# LIM_LEDS_POWER.net
KiCad netlist of a schematic drawn in Altium Designer
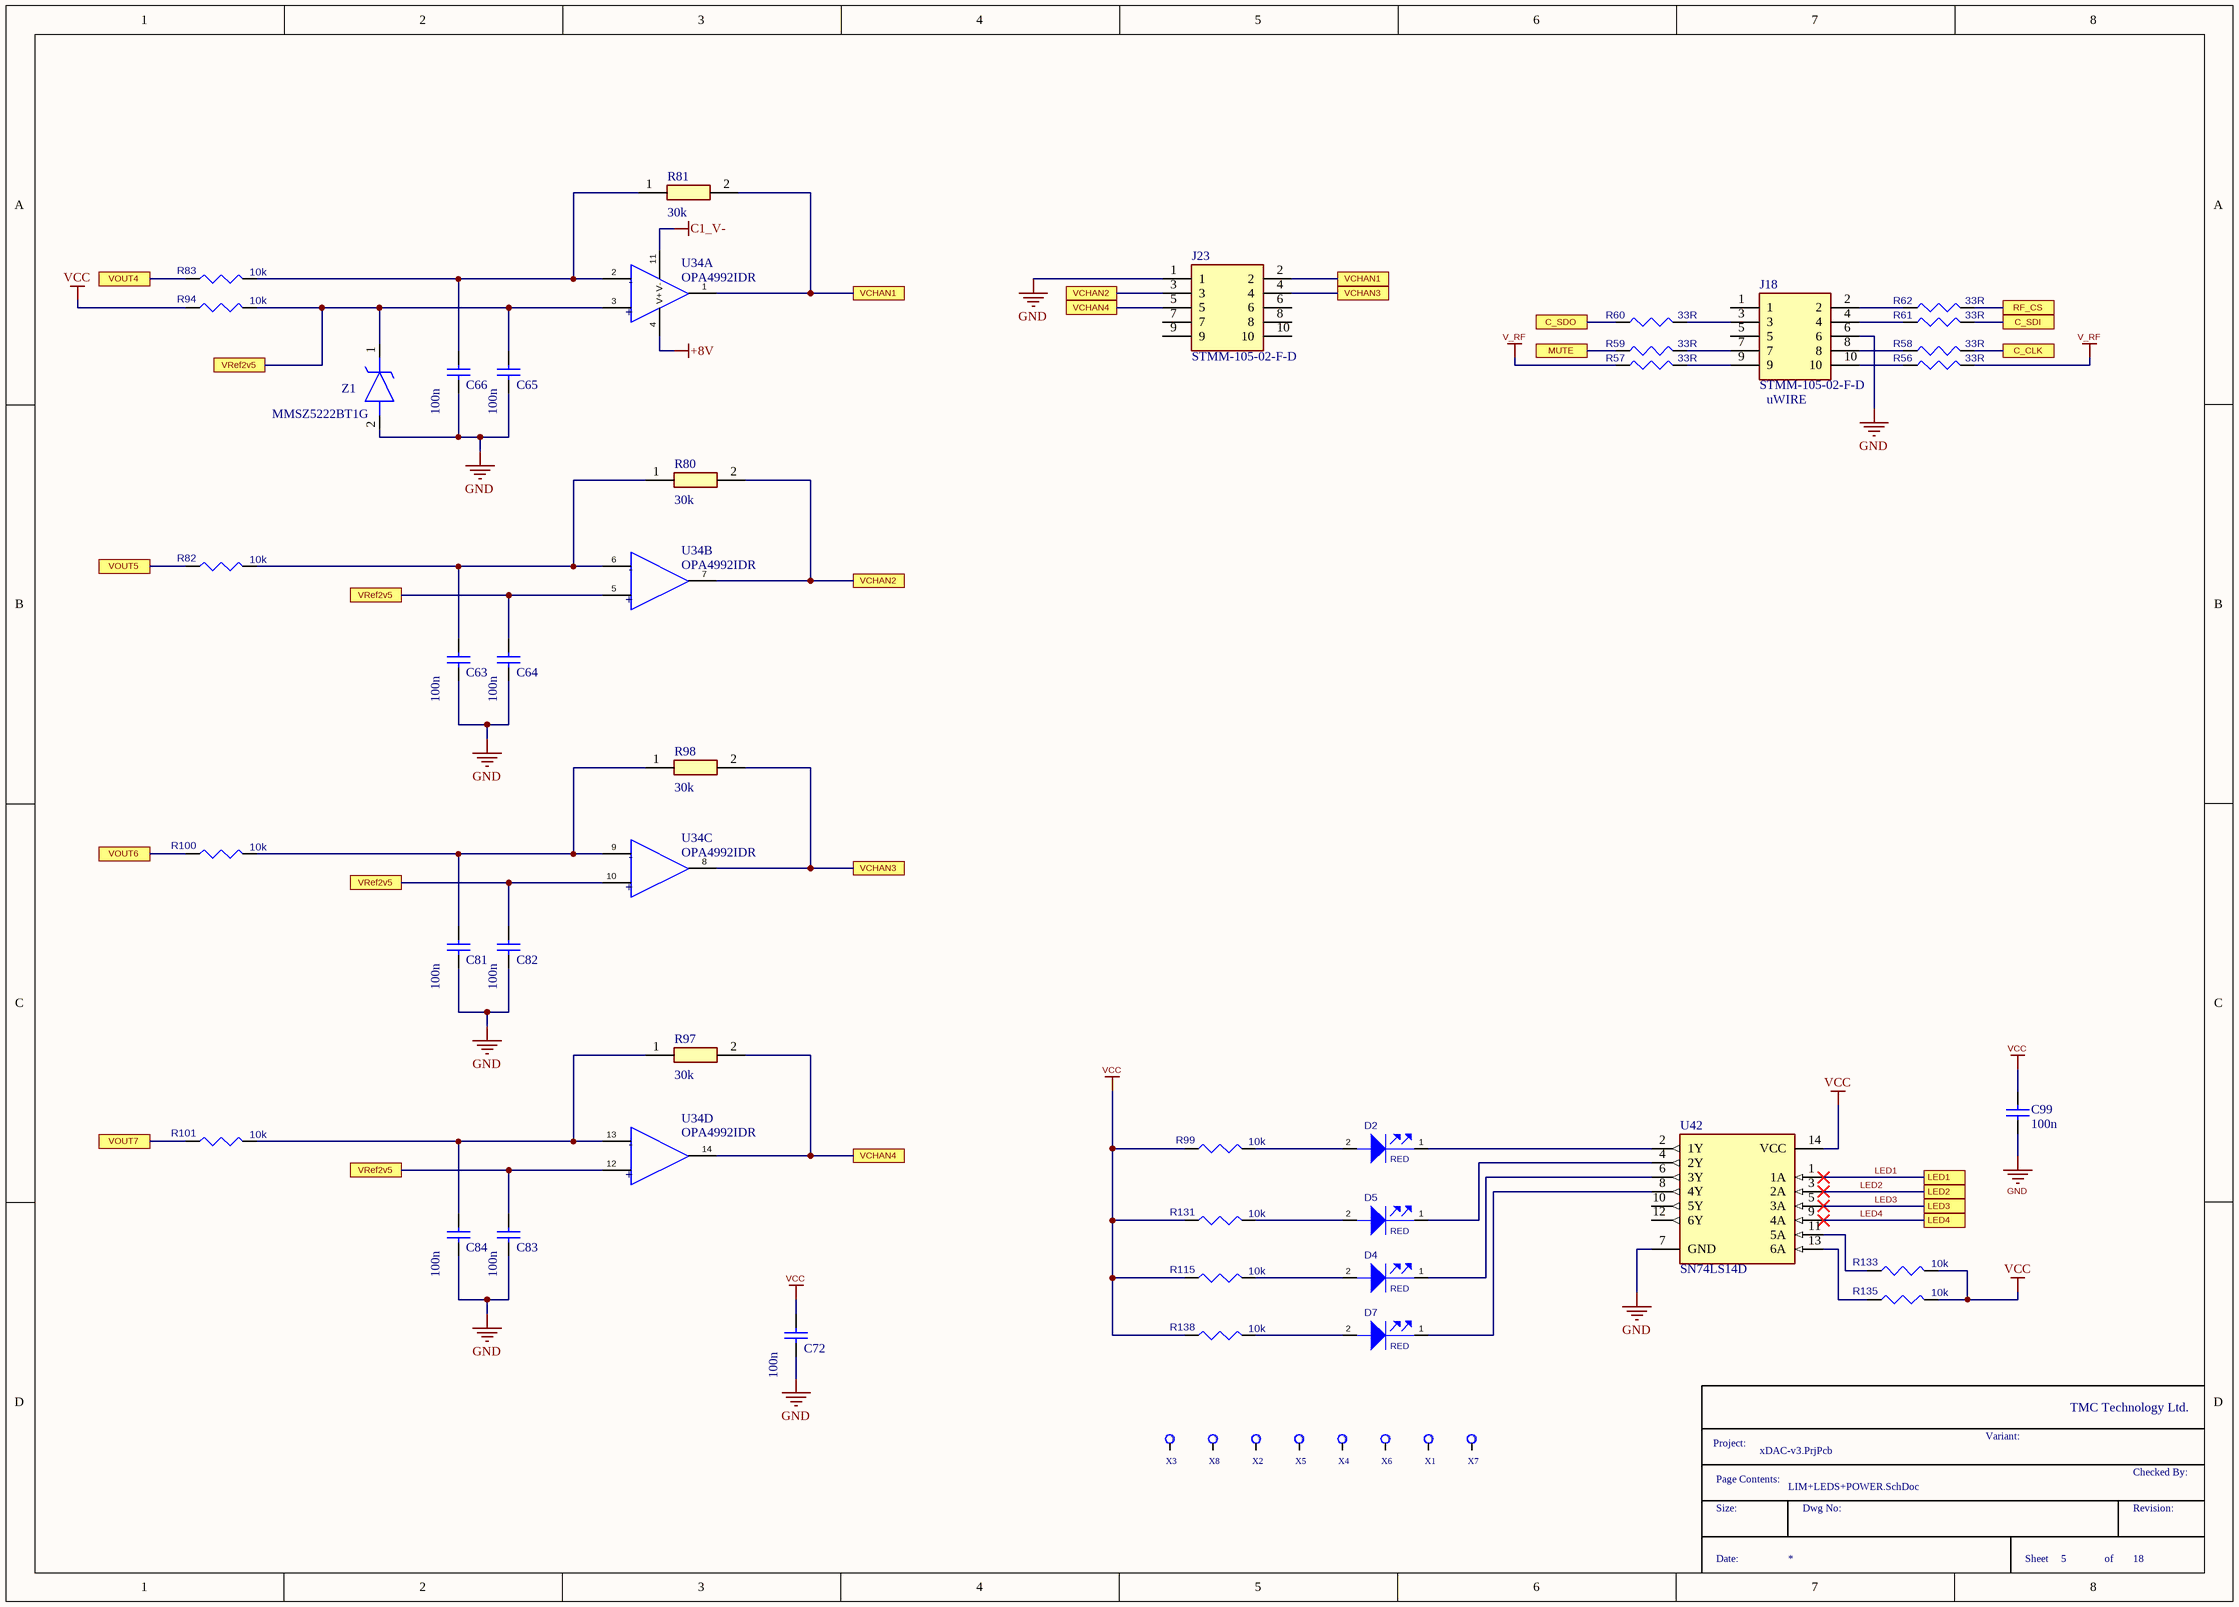
[diagram p0: LIM+LEDS+POWER.SchDoc]

(export (version "E")
  (design (tool "Eeschema 10.0.6"))
  (components
    (comp (ref "C63")
      (value "100n")
      (footprint "CAPC1608X90X35LL15T15")
      (description "Chip Capacitor, 100 nF, +/- 10%, 50 V, -55 to 125 degC, 0603 (1608 Metric), RoHS, Tape and Reel")
      (fields (field (name "TOLERANCE") "10%") (field (name "MANUFACTURER") "KEMET"))
      (libsource (lib "xDAC_Carrier") (part "CMP-1035-02592-3"))
    )
    (comp (ref "C64")
      (value "100n")
      (footprint "CAPC1608X90X35LL15T15")
      (description "Chip Capacitor, 100 nF, +/- 10%, 50 V, -55 to 125 degC, 0603 (1608 Metric), RoHS, Tape and Reel")
      (fields (field (name "TOLERANCE") "10%") (field (name "MANUFACTURER") "KEMET"))
      (libsource (lib "xDAC_Carrier") (part "CMP-1035-02592-3"))
    )
    (comp (ref "C65")
      (value "100n")
      (footprint "CAPC1608X90X35LL15T15")
      (description "Chip Capacitor, 100 nF, +/- 10%, 50 V, -55 to 125 degC, 0603 (1608 Metric), RoHS, Tape and Reel")
      (fields (field (name "TOLERANCE") "10%") (field (name "MANUFACTURER") "KEMET"))
      (libsource (lib "xDAC_Carrier") (part "CMP-1035-02592-3"))
    )
    (comp (ref "C66")
      (value "100n")
      (footprint "CAPC1608X90X35LL15T15")
      (description "Chip Capacitor, 100 nF, +/- 10%, 50 V, -55 to 125 degC, 0603 (1608 Metric), RoHS, Tape and Reel")
      (fields (field (name "TOLERANCE") "10%") (field (name "MANUFACTURER") "KEMET"))
      (libsource (lib "xDAC_Carrier") (part "CMP-1035-02592-3"))
    )
    (comp (ref "C72")
      (value "100n")
      (footprint "CAPC1608X90X35LL15T15")
      (description "Chip Capacitor, 100 nF, +/- 10%, 50 V, -55 to 125 degC, 0603 (1608 Metric), RoHS, Tape and Reel")
      (fields (field (name "TOLERANCE") "10%") (field (name "MANUFACTURER") "KEMET"))
      (libsource (lib "xDAC_Carrier") (part "CMP-1035-02592-3"))
    )
    (comp (ref "C81")
      (value "100n")
      (footprint "CAPC1608X90X35LL15T15")
      (description "Chip Capacitor, 100 nF, +/- 10%, 50 V, -55 to 125 degC, 0603 (1608 Metric), RoHS, Tape and Reel")
      (fields (field (name "TOLERANCE") "10%") (field (name "MANUFACTURER") "KEMET"))
      (libsource (lib "xDAC_Carrier") (part "CMP-1035-02592-3"))
    )
    (comp (ref "C82")
      (value "100n")
      (footprint "CAPC1608X90X35LL15T15")
      (description "Chip Capacitor, 100 nF, +/- 10%, 50 V, -55 to 125 degC, 0603 (1608 Metric), RoHS, Tape and Reel")
      (fields (field (name "TOLERANCE") "10%") (field (name "MANUFACTURER") "KEMET"))
      (libsource (lib "xDAC_Carrier") (part "CMP-1035-02592-3"))
    )
    (comp (ref "C83")
      (value "100n")
      (footprint "CAPC1608X90X35LL15T15")
      (description "Chip Capacitor, 100 nF, +/- 10%, 50 V, -55 to 125 degC, 0603 (1608 Metric), RoHS, Tape and Reel")
      (fields (field (name "TOLERANCE") "10%") (field (name "MANUFACTURER") "KEMET"))
      (libsource (lib "xDAC_Carrier") (part "CMP-1035-02592-3"))
    )
    (comp (ref "C84")
      (value "100n")
      (footprint "CAPC1608X90X35LL15T15")
      (description "Chip Capacitor, 100 nF, +/- 10%, 50 V, -55 to 125 degC, 0603 (1608 Metric), RoHS, Tape and Reel")
      (fields (field (name "TOLERANCE") "10%") (field (name "MANUFACTURER") "KEMET"))
      (libsource (lib "xDAC_Carrier") (part "CMP-1035-02592-3"))
    )
    (comp (ref "C99")
      (value "100n")
      (footprint "CAPC1608X90X35LL15T15")
      (description "Chip Capacitor, 100 nF, +/- 10%, 50 V, -55 to 125 degC, 0603 (1608 Metric), RoHS, Tape and Reel")
      (fields (field (name "TOLERANCE") "10%") (field (name "MANUFACTURER") "KEMET"))
      (libsource (lib "xDAC_Carrier") (part "CMP-1035-02592-3"))
    )
    (comp (ref "D2")
      (value "RED")
      (footprint "LED$2F$RA")
      (description "LED,RED,WATERCLEAR,TH RA")
      (fields (field (name "MANUFACTURER") "BROADCOM") (field (name "PART NO") "HLMP-3301-F00B2"))
      (libsource (lib "xDAC_Carrier") (part "LED"))
    )
    (comp (ref "D4")
      (value "RED")
      (footprint "LED$2F$RA")
      (description "LED,RED,WATERCLEAR,TH RA")
      (fields (field (name "MANUFACTURER") "BROADCOM") (field (name "PART NO") "HLMP-3301-F00B2"))
      (libsource (lib "xDAC_Carrier") (part "LED"))
    )
    (comp (ref "D5")
      (value "RED")
      (footprint "LED$2F$RA")
      (description "LED,RED,WATERCLEAR,TH RA")
      (fields (field (name "MANUFACTURER") "BROADCOM") (field (name "PART NO") "HLMP-3301-F00B2"))
      (libsource (lib "xDAC_Carrier") (part "LED"))
    )
    (comp (ref "D7")
      (value "RED")
      (footprint "LED$2F$RA")
      (description "LED,RED,WATERCLEAR,TH RA")
      (fields (field (name "MANUFACTURER") "BROADCOM") (field (name "PART NO") "HLMP-3301-F00B2"))
      (libsource (lib "xDAC_Carrier") (part "LED"))
    )
    (comp (ref "J18")
      (value "STMM-105-02-F-D")
      (footprint "STMM-105-XX-YY-D")
      (description "Connector")
      (fields (field (name "MOUSER PART NUMBER") "200-STMM10502FD") (field (name "ALTIUM_VALUE") "uWIRE"))
      (libsource (lib "xDAC_Carrier") (part "STMM-105-02-F-D"))
    )
    (comp (ref "J23")
      (value "STMM-105-02-F-D")
      (footprint "STMM-105-XX-YY-D")
      (description "Connector")
      (fields (field (name "MOUSER PART NUMBER") "200-STMM10502FD"))
      (libsource (lib "xDAC_Carrier") (part "STMM-105-02-F-D"))
    )
    (comp (ref "R56")
      (value "33R")
      (footprint "CR0603N")
      (description "RES.,10k OHMS,1%,1/10W,0603")
      (fields (field (name "MANUFACTURER") "PANASONIC") (field (name "TOLERANCE") "1%"))
      (libsource (lib "xDAC_Carrier") (part "RES"))
    )
    (comp (ref "R57")
      (value "33R")
      (footprint "CR0603N")
      (description "RES.,10k OHMS,1%,1/10W,0603")
      (fields (field (name "MANUFACTURER") "PANASONIC") (field (name "TOLERANCE") "1%"))
      (libsource (lib "xDAC_Carrier") (part "RES"))
    )
    (comp (ref "R58")
      (value "33R")
      (footprint "CR0603N")
      (description "RES.,10k OHMS,1%,1/10W,0603")
      (fields (field (name "MANUFACTURER") "PANASONIC") (field (name "TOLERANCE") "1%"))
      (libsource (lib "xDAC_Carrier") (part "RES"))
    )
    (comp (ref "R59")
      (value "33R")
      (footprint "CR0603N")
      (description "RES.,10k OHMS,1%,1/10W,0603")
      (fields (field (name "MANUFACTURER") "PANASONIC") (field (name "TOLERANCE") "1%"))
      (libsource (lib "xDAC_Carrier") (part "RES"))
    )
    (comp (ref "R60")
      (value "33R")
      (footprint "CR0603N")
      (description "RES.,10k OHMS,1%,1/10W,0603")
      (fields (field (name "MANUFACTURER") "PANASONIC") (field (name "TOLERANCE") "1%"))
      (libsource (lib "xDAC_Carrier") (part "RES"))
    )
    (comp (ref "R61")
      (value "33R")
      (footprint "CR0603N")
      (description "RES.,10k OHMS,1%,1/10W,0603")
      (fields (field (name "MANUFACTURER") "PANASONIC") (field (name "TOLERANCE") "1%"))
      (libsource (lib "xDAC_Carrier") (part "RES"))
    )
    (comp (ref "R62")
      (value "33R")
      (footprint "CR0603N")
      (description "RES.,10k OHMS,1%,1/10W,0603")
      (fields (field (name "MANUFACTURER") "PANASONIC") (field (name "TOLERANCE") "1%"))
      (libsource (lib "xDAC_Carrier") (part "RES"))
    )
    (comp (ref "R80")
      (value "30k")
      (footprint "ERJS03J155V")
      (description "Resistor")
      (fields (field (name "MANUFACTURER_PART_NUMBER") "ERJ-U03F3002V"))
      (libsource (lib "Pilot") (part "ERJ-U03F3002V"))
    )
    (comp (ref "R81")
      (value "30k")
      (footprint "ERJS03J155V")
      (description "Resistor")
      (fields (field (name "MANUFACTURER_PART_NUMBER") "ERJ-U03F3002V"))
      (libsource (lib "Pilot") (part "ERJ-U03F3002V"))
    )
    (comp (ref "R82")
      (value "10k")
      (footprint "CR0603N")
      (description "RES.,10k OHMS,1%,1/10W,0603")
      (fields (field (name "MANUFACTURER") "PANASONIC") (field (name "TOLERANCE") "1%"))
      (libsource (lib "xDAC_Carrier") (part "RES"))
    )
    (comp (ref "R83")
      (value "10k")
      (footprint "CR0603N")
      (description "RES.,10k OHMS,1%,1/10W,0603")
      (fields (field (name "MANUFACTURER") "PANASONIC") (field (name "TOLERANCE") "1%"))
      (libsource (lib "xDAC_Carrier") (part "RES"))
    )
    (comp (ref "R94")
      (value "10k")
      (footprint "CR0603N")
      (description "RES.,10k OHMS,1%,1/10W,0603")
      (fields (field (name "MANUFACTURER") "PANASONIC") (field (name "TOLERANCE") "1%"))
      (libsource (lib "xDAC_Carrier") (part "RES"))
    )
    (comp (ref "R97")
      (value "30k")
      (footprint "ERJS03J155V")
      (description "Resistor")
      (fields (field (name "MANUFACTURER_PART_NUMBER") "ERJ-U03F3002V"))
      (libsource (lib "Pilot") (part "ERJ-U03F3002V"))
    )
    (comp (ref "R98")
      (value "30k")
      (footprint "ERJS03J155V")
      (description "Resistor")
      (fields (field (name "MANUFACTURER_PART_NUMBER") "ERJ-U03F3002V"))
      (libsource (lib "Pilot") (part "ERJ-U03F3002V"))
    )
    (comp (ref "R99")
      (value "10k")
      (footprint "CR0603N")
      (description "RES.,10k OHMS,1%,1/10W,0603")
      (fields (field (name "MANUFACTURER") "PANASONIC") (field (name "TOLERANCE") "1%"))
      (libsource (lib "xDAC_Carrier") (part "RES"))
    )
    (comp (ref "R100")
      (value "10k")
      (footprint "CR0603N")
      (description "RES.,10k OHMS,1%,1/10W,0603")
      (fields (field (name "MANUFACTURER") "PANASONIC") (field (name "TOLERANCE") "1%"))
      (libsource (lib "xDAC_Carrier") (part "RES"))
    )
    (comp (ref "R101")
      (value "10k")
      (footprint "CR0603N")
      (description "RES.,10k OHMS,1%,1/10W,0603")
      (fields (field (name "MANUFACTURER") "PANASONIC") (field (name "TOLERANCE") "1%"))
      (libsource (lib "xDAC_Carrier") (part "RES"))
    )
    (comp (ref "R115")
      (value "10k")
      (footprint "CR0603N")
      (description "RES.,10k OHMS,1%,1/10W,0603")
      (fields (field (name "MANUFACTURER") "PANASONIC") (field (name "TOLERANCE") "1%"))
      (libsource (lib "xDAC_Carrier") (part "RES"))
    )
    (comp (ref "R131")
      (value "10k")
      (footprint "CR0603N")
      (description "RES.,10k OHMS,1%,1/10W,0603")
      (fields (field (name "MANUFACTURER") "PANASONIC") (field (name "TOLERANCE") "1%"))
      (libsource (lib "xDAC_Carrier") (part "RES"))
    )
    (comp (ref "R133")
      (value "10k")
      (footprint "CR0603N")
      (description "RES.,10k OHMS,1%,1/10W,0603")
      (fields (field (name "MANUFACTURER") "PANASONIC") (field (name "TOLERANCE") "1%"))
      (libsource (lib "xDAC_Carrier") (part "RES"))
    )
    (comp (ref "R135")
      (value "10k")
      (footprint "CR0603N")
      (description "RES.,10k OHMS,1%,1/10W,0603")
      (fields (field (name "MANUFACTURER") "PANASONIC") (field (name "TOLERANCE") "1%"))
      (libsource (lib "xDAC_Carrier") (part "RES"))
    )
    (comp (ref "R138")
      (value "10k")
      (footprint "CR0603N")
      (description "RES.,10k OHMS,1%,1/10W,0603")
      (fields (field (name "MANUFACTURER") "PANASONIC") (field (name "TOLERANCE") "1%"))
      (libsource (lib "xDAC_Carrier") (part "RES"))
    )
    (comp (ref "U34")
      (value "OPA4992IDR")
      (footprint "SOIC127P600X175-14N")
      (description "Integrated Circuit")
      (fields (field (name "MOUSER PART NUMBER") "595-OPA4992IDR"))
      (libsource (lib "xDAC_Carrier") (part "OPA4992IDR"))
    )
    (comp (ref "U42")
      (value "SN74LS14D")
      (footprint "FP-D0014A-MFG")
      (description "IC INVERTER SCHMITT 6CH 14SOIC")
      (fields
        (field (name "OCTOPART") "https://octopart.com/sn74ls14d-texas+instruments-464458")
        (field (name "MANUFACTURER") "Texas Instruments")
      )
      (libsource (lib "Altium Content Vault") (part "988d500a1b54a36af656cee24e4e601"))
    )
    (comp (ref "X1")
      (value "MTG3MM")
      (footprint "MTG3MM")
      (description ".128 MOUNTING HOLE / .250 PAD")
      (fields
        (field (name "PART NUMBER") "MTHOLE1")
        (field (name "CREATED BY") "CADPRO, SAN DIEGO, CA  (619) 552-1475")
      )
      (libsource (lib "xDAC_Carrier") (part "MTG3MM"))
    )
    (comp (ref "X2")
      (value "MTG3MM")
      (footprint "MTG3MM")
      (description ".128 MOUNTING HOLE / .250 PAD")
      (fields
        (field (name "PART NUMBER") "MTHOLE1")
        (field (name "CREATED BY") "CADPRO, SAN DIEGO, CA  (619) 552-1475")
      )
      (libsource (lib "xDAC_Carrier") (part "MTG3MM"))
    )
    (comp (ref "X3")
      (value "MTG3MM")
      (footprint "MTG3MM")
      (description ".128 MOUNTING HOLE / .250 PAD")
      (fields
        (field (name "PART NUMBER") "MTHOLE1")
        (field (name "CREATED BY") "CADPRO, SAN DIEGO, CA  (619) 552-1475")
      )
      (libsource (lib "xDAC_Carrier") (part "MTG3MM"))
    )
    (comp (ref "X4")
      (value "MTG3MM")
      (footprint "MTG3MM")
      (description ".128 MOUNTING HOLE / .250 PAD")
      (fields
        (field (name "PART NUMBER") "MTHOLE1")
        (field (name "CREATED BY") "CADPRO, SAN DIEGO, CA  (619) 552-1475")
      )
      (libsource (lib "xDAC_Carrier") (part "MTG3MM"))
    )
    (comp (ref "X5")
      (value "MTG3MM")
      (footprint "MTG3MM")
      (description ".128 MOUNTING HOLE / .250 PAD")
      (fields
        (field (name "PART NUMBER") "MTHOLE1")
        (field (name "CREATED BY") "CADPRO, SAN DIEGO, CA  (619) 552-1475")
      )
      (libsource (lib "xDAC_Carrier") (part "MTG3MM"))
    )
    (comp (ref "X6")
      (value "MTG3MM")
      (footprint "MTG3MM")
      (description ".128 MOUNTING HOLE / .250 PAD")
      (fields
        (field (name "PART NUMBER") "MTHOLE1")
        (field (name "CREATED BY") "CADPRO, SAN DIEGO, CA  (619) 552-1475")
      )
      (libsource (lib "xDAC_Carrier") (part "MTG3MM"))
    )
    (comp (ref "X7")
      (value "MTG3MM")
      (footprint "MTG3MM")
      (description ".128 MOUNTING HOLE / .250 PAD")
      (fields
        (field (name "PART NUMBER") "MTHOLE1")
        (field (name "CREATED BY") "CADPRO, SAN DIEGO, CA  (619) 552-1475")
      )
      (libsource (lib "xDAC_Carrier") (part "MTG3MM"))
    )
    (comp (ref "X8")
      (value "MTG3MM")
      (footprint "MTG3MM")
      (description ".128 MOUNTING HOLE / .250 PAD")
      (fields
        (field (name "PART NUMBER") "MTHOLE1")
        (field (name "CREATED BY") "CADPRO, SAN DIEGO, CA  (619) 552-1475")
      )
      (libsource (lib "xDAC_Carrier") (part "MTG3MM"))
    )
    (comp (ref "Z1")
      (value "MMSZ5222BT1G")
      (footprint "SOD3716X135N")
      (description "Zener Diode")
      (fields (field (name "MOUSER PART NUMBER") "863-MMSZ5222BT1G"))
      (libsource (lib "xDAC_Carrier") (part "MMSZ5222BT1G"))
    )
  )
  (nets
    (net (code "1") (name "+8V") (class "Default")
      (node (ref "U34") (pin "4") (pinfunction "V+_4") (pintype "passive"))
    )
    (net (code "2") (name "/C_CLK") (class "Default")
      (node (ref "R58") (pin "2") (pinfunction "2_2") (pintype "passive"))
    )
    (net (code "3") (name "/C_SDI") (class "Default")
      (node (ref "R61") (pin "2") (pinfunction "2_2") (pintype "passive"))
    )
    (net (code "4") (name "/C_SDO") (class "Default")
      (node (ref "R60") (pin "1") (pinfunction "1_1") (pintype "passive"))
    )
    (net (code "5") (name "/LED1") (class "Default")
      (node (ref "U42") (pin "1") (pinfunction "1A_1") (pintype "input+no_connect"))
    )
    (net (code "6") (name "/LED2") (class "Default")
      (node (ref "U42") (pin "3") (pinfunction "2A_3") (pintype "input+no_connect"))
    )
    (net (code "7") (name "/LED3") (class "Default")
      (node (ref "U42") (pin "5") (pinfunction "3A_5") (pintype "input+no_connect"))
    )
    (net (code "8") (name "/LED4") (class "Default")
      (node (ref "U42") (pin "9") (pinfunction "4A_9") (pintype "input+no_connect"))
    )
    (net (code "9") (name "/MUTE") (class "Default")
      (node (ref "R59") (pin "1") (pinfunction "1_1") (pintype "passive"))
    )
    (net (code "10") (name "/RF_CS") (class "Default")
      (node (ref "R62") (pin "2") (pinfunction "2_2") (pintype "passive"))
    )
    (net (code "11") (name "/VCHAN1") (class "Default")
      (node (ref "J23") (pin "2") (pinfunction "2_2") (pintype "passive"))
      (node (ref "R81") (pin "2") (pinfunction "2_2") (pintype "passive"))
      (node (ref "U34") (pin "1") (pinfunction "1_1") (pintype "passive"))
    )
    (net (code "12") (name "/VCHAN2") (class "Default")
      (node (ref "J23") (pin "3") (pinfunction "3_3") (pintype "passive"))
      (node (ref "R80") (pin "2") (pinfunction "2_2") (pintype "passive"))
      (node (ref "U34") (pin "7") (pinfunction "7_7") (pintype "passive"))
    )
    (net (code "13") (name "/VCHAN3") (class "Default")
      (node (ref "J23") (pin "4") (pinfunction "4_4") (pintype "passive"))
      (node (ref "R98") (pin "2") (pinfunction "2_2") (pintype "passive"))
      (node (ref "U34") (pin "8") (pinfunction "8_8") (pintype "passive"))
    )
    (net (code "14") (name "/VCHAN4") (class "Default")
      (node (ref "J23") (pin "5") (pinfunction "5_5") (pintype "passive"))
      (node (ref "R97") (pin "2") (pinfunction "2_2") (pintype "passive"))
      (node (ref "U34") (pin "14") (pinfunction "14_14") (pintype "passive"))
    )
    (net (code "15") (name "/VOUT4") (class "Default")
      (node (ref "R83") (pin "1") (pinfunction "1_1") (pintype "passive"))
    )
    (net (code "16") (name "/VOUT5") (class "Default")
      (node (ref "R82") (pin "1") (pinfunction "1_1") (pintype "passive"))
    )
    (net (code "17") (name "/VOUT6") (class "Default")
      (node (ref "R100") (pin "1") (pinfunction "1_1") (pintype "passive"))
    )
    (net (code "18") (name "/VOUT7") (class "Default")
      (node (ref "R101") (pin "1") (pinfunction "1_1") (pintype "passive"))
    )
    (net (code "19") (name "/VRef2v5") (class "Default")
      (node (ref "C64") (pin "1") (pinfunction "1_1") (pintype "passive"))
      (node (ref "C65") (pin "1") (pinfunction "1_1") (pintype "passive"))
      (node (ref "C82") (pin "1") (pinfunction "1_1") (pintype "passive"))
      (node (ref "C83") (pin "1") (pinfunction "1_1") (pintype "passive"))
      (node (ref "R94") (pin "2") (pinfunction "2_2") (pintype "passive"))
      (node (ref "U34") (pin "10") (pinfunction "10_10") (pintype "passive"))
      (node (ref "U34") (pin "12") (pinfunction "12_12") (pintype "passive"))
      (node (ref "U34") (pin "3") (pinfunction "3_3") (pintype "passive"))
      (node (ref "U34") (pin "5") (pinfunction "5_5") (pintype "passive"))
      (node (ref "Z1") (pin "1") (pinfunction "K_1") (pintype "passive"))
    )
    (net (code "20") (name "C1_V-") (class "Default")
      (node (ref "U34") (pin "11") (pinfunction "V-_11") (pintype "passive"))
    )
    (net (code "21") (name "GND") (class "Default")
      (node (ref "C63") (pin "2") (pinfunction "2_2") (pintype "passive"))
      (node (ref "C64") (pin "2") (pinfunction "2_2") (pintype "passive"))
      (node (ref "C65") (pin "2") (pinfunction "2_2") (pintype "passive"))
      (node (ref "C66") (pin "2") (pinfunction "2_2") (pintype "passive"))
      (node (ref "C72") (pin "2") (pinfunction "2_2") (pintype "passive"))
      (node (ref "C81") (pin "2") (pinfunction "2_2") (pintype "passive"))
      (node (ref "C82") (pin "2") (pinfunction "2_2") (pintype "passive"))
      (node (ref "C83") (pin "2") (pinfunction "2_2") (pintype "passive"))
      (node (ref "C84") (pin "2") (pinfunction "2_2") (pintype "passive"))
      (node (ref "C99") (pin "2") (pinfunction "2_2") (pintype "passive"))
      (node (ref "J18") (pin "6") (pinfunction "6_6") (pintype "passive"))
      (node (ref "J23") (pin "1") (pinfunction "1_1") (pintype "passive"))
      (node (ref "U42") (pin "7") (pinfunction "GND_7") (pintype "passive"))
      (node (ref "Z1") (pin "2") (pinfunction "A_2") (pintype "passive"))
    )
    (net (code "22") (name "Net-(C63-Pad1)") (class "Default")
      (node (ref "C63") (pin "1") (pinfunction "1_1") (pintype "passive"))
      (node (ref "R80") (pin "1") (pinfunction "1_1") (pintype "passive"))
      (node (ref "R82") (pin "2") (pinfunction "2_2") (pintype "passive"))
      (node (ref "U34") (pin "6") (pinfunction "6_6") (pintype "passive"))
    )
    (net (code "23") (name "Net-(C66-Pad1)") (class "Default")
      (node (ref "C66") (pin "1") (pinfunction "1_1") (pintype "passive"))
      (node (ref "R81") (pin "1") (pinfunction "1_1") (pintype "passive"))
      (node (ref "R83") (pin "2") (pinfunction "2_2") (pintype "passive"))
      (node (ref "U34") (pin "2") (pinfunction "2_2") (pintype "passive"))
    )
    (net (code "24") (name "Net-(C81-Pad1)") (class "Default")
      (node (ref "C81") (pin "1") (pinfunction "1_1") (pintype "passive"))
      (node (ref "R100") (pin "2") (pinfunction "2_2") (pintype "passive"))
      (node (ref "R98") (pin "1") (pinfunction "1_1") (pintype "passive"))
      (node (ref "U34") (pin "9") (pinfunction "9_9") (pintype "passive"))
    )
    (net (code "25") (name "Net-(C84-Pad1)") (class "Default")
      (node (ref "C84") (pin "1") (pinfunction "1_1") (pintype "passive"))
      (node (ref "R101") (pin "2") (pinfunction "2_2") (pintype "passive"))
      (node (ref "R97") (pin "1") (pinfunction "1_1") (pintype "passive"))
      (node (ref "U34") (pin "13") (pinfunction "13_13") (pintype "passive"))
    )
    (net (code "26") (name "Net-(D2-ANODE)") (class "Default")
      (node (ref "D2") (pin "2") (pinfunction "ANODE_2") (pintype "passive"))
      (node (ref "R99") (pin "2") (pinfunction "2_2") (pintype "passive"))
    )
    (net (code "27") (name "Net-(D2-CATHODE)") (class "Default")
      (node (ref "D2") (pin "1") (pinfunction "CATHODE_1") (pintype "passive"))
      (node (ref "U42") (pin "2") (pinfunction "1Y_2") (pintype "output"))
    )
    (net (code "28") (name "Net-(D4-ANODE)") (class "Default")
      (node (ref "D4") (pin "2") (pinfunction "ANODE_2") (pintype "passive"))
      (node (ref "R115") (pin "2") (pinfunction "2_2") (pintype "passive"))
    )
    (net (code "29") (name "Net-(D4-CATHODE)") (class "Default")
      (node (ref "D4") (pin "1") (pinfunction "CATHODE_1") (pintype "passive"))
      (node (ref "U42") (pin "6") (pinfunction "3Y_6") (pintype "output"))
    )
    (net (code "30") (name "Net-(D5-ANODE)") (class "Default")
      (node (ref "D5") (pin "2") (pinfunction "ANODE_2") (pintype "passive"))
      (node (ref "R131") (pin "2") (pinfunction "2_2") (pintype "passive"))
    )
    (net (code "31") (name "Net-(D5-CATHODE)") (class "Default")
      (node (ref "D5") (pin "1") (pinfunction "CATHODE_1") (pintype "passive"))
      (node (ref "U42") (pin "4") (pinfunction "2Y_4") (pintype "output"))
    )
    (net (code "32") (name "Net-(D7-ANODE)") (class "Default")
      (node (ref "D7") (pin "2") (pinfunction "ANODE_2") (pintype "passive"))
      (node (ref "R138") (pin "2") (pinfunction "2_2") (pintype "passive"))
    )
    (net (code "33") (name "Net-(D7-CATHODE)") (class "Default")
      (node (ref "D7") (pin "1") (pinfunction "CATHODE_1") (pintype "passive"))
      (node (ref "U42") (pin "8") (pinfunction "4Y_8") (pintype "output"))
    )
    (net (code "34") (name "Net-(J18-Pad2)") (class "Default")
      (node (ref "J18") (pin "2") (pinfunction "2_2") (pintype "passive"))
      (node (ref "R62") (pin "1") (pinfunction "1_1") (pintype "passive"))
    )
    (net (code "35") (name "Net-(J18-Pad3)") (class "Default")
      (node (ref "J18") (pin "3") (pinfunction "3_3") (pintype "passive"))
      (node (ref "R60") (pin "2") (pinfunction "2_2") (pintype "passive"))
    )
    (net (code "36") (name "Net-(J18-Pad4)") (class "Default")
      (node (ref "J18") (pin "4") (pinfunction "4_4") (pintype "passive"))
      (node (ref "R61") (pin "1") (pinfunction "1_1") (pintype "passive"))
    )
    (net (code "37") (name "Net-(J18-Pad7)") (class "Default")
      (node (ref "J18") (pin "7") (pinfunction "7_7") (pintype "passive"))
      (node (ref "R59") (pin "2") (pinfunction "2_2") (pintype "passive"))
    )
    (net (code "38") (name "Net-(J18-Pad8)") (class "Default")
      (node (ref "J18") (pin "8") (pinfunction "8_8") (pintype "passive"))
      (node (ref "R58") (pin "1") (pinfunction "1_1") (pintype "passive"))
    )
    (net (code "39") (name "Net-(J18-Pad9)") (class "Default")
      (node (ref "J18") (pin "9") (pinfunction "9_9") (pintype "passive"))
      (node (ref "R57") (pin "2") (pinfunction "2_2") (pintype "passive"))
    )
    (net (code "40") (name "Net-(J18-Pad10)") (class "Default")
      (node (ref "J18") (pin "10") (pinfunction "10_10") (pintype "passive"))
      (node (ref "R56") (pin "1") (pinfunction "1_1") (pintype "passive"))
    )
    (net (code "41") (name "Net-(U42-5A)") (class "Default")
      (node (ref "R133") (pin "1") (pinfunction "1_1") (pintype "passive"))
      (node (ref "U42") (pin "11") (pinfunction "5A_11") (pintype "input"))
    )
    (net (code "42") (name "Net-(U42-6A)") (class "Default")
      (node (ref "R135") (pin "1") (pinfunction "1_1") (pintype "passive"))
      (node (ref "U42") (pin "13") (pinfunction "6A_13") (pintype "input"))
    )
    (net (code "43") (name "VCC") (class "Default")
      (node (ref "C72") (pin "1") (pinfunction "1_1") (pintype "passive"))
      (node (ref "C99") (pin "1") (pinfunction "1_1") (pintype "passive"))
      (node (ref "R115") (pin "1") (pinfunction "1_1") (pintype "passive"))
      (node (ref "R131") (pin "1") (pinfunction "1_1") (pintype "passive"))
      (node (ref "R133") (pin "2") (pinfunction "2_2") (pintype "passive"))
      (node (ref "R135") (pin "2") (pinfunction "2_2") (pintype "passive"))
      (node (ref "R138") (pin "1") (pinfunction "1_1") (pintype "passive"))
      (node (ref "R94") (pin "1") (pinfunction "1_1") (pintype "passive"))
      (node (ref "R99") (pin "1") (pinfunction "1_1") (pintype "passive"))
      (node (ref "U42") (pin "14") (pinfunction "VCC_14") (pintype "power_in"))
    )
    (net (code "44") (name "V_RF") (class "Default")
      (node (ref "R56") (pin "2") (pinfunction "2_2") (pintype "passive"))
      (node (ref "R57") (pin "1") (pinfunction "1_1") (pintype "passive"))
    )
    (net (code "45") (name "unconnected-(J18-Pad1)") (class "Default")
      (node (ref "J18") (pin "1") (pinfunction "1_1") (pintype "passive"))
    )
    (net (code "46") (name "unconnected-(J18-Pad5)") (class "Default")
      (node (ref "J18") (pin "5") (pinfunction "5_5") (pintype "passive"))
    )
    (net (code "47") (name "unconnected-(J23-Pad6)") (class "Default")
      (node (ref "J23") (pin "6") (pinfunction "6_6") (pintype "passive"))
    )
    (net (code "48") (name "unconnected-(J23-Pad7)") (class "Default")
      (node (ref "J23") (pin "7") (pinfunction "7_7") (pintype "passive"))
    )
    (net (code "49") (name "unconnected-(J23-Pad8)") (class "Default")
      (node (ref "J23") (pin "8") (pinfunction "8_8") (pintype "passive"))
    )
    (net (code "50") (name "unconnected-(J23-Pad9)") (class "Default")
      (node (ref "J23") (pin "9") (pinfunction "9_9") (pintype "passive"))
    )
    (net (code "51") (name "unconnected-(J23-Pad10)") (class "Default")
      (node (ref "J23") (pin "10") (pinfunction "10_10") (pintype "passive"))
    )
    (net (code "52") (name "unconnected-(U42-5Y-Pad10)") (class "Default")
      (node (ref "U42") (pin "10") (pinfunction "5Y_10") (pintype "output"))
    )
    (net (code "53") (name "unconnected-(U42-6Y-Pad12)") (class "Default")
      (node (ref "U42") (pin "12") (pinfunction "6Y_12") (pintype "output"))
    )
    (net (code "54") (name "unconnected-(X1-Pad1)") (class "Default")
      (node (ref "X1") (pin "1") (pinfunction "1_1") (pintype "passive"))
    )
    (net (code "55") (name "unconnected-(X2-Pad1)") (class "Default")
      (node (ref "X2") (pin "1") (pinfunction "1_1") (pintype "passive"))
    )
    (net (code "56") (name "unconnected-(X3-Pad1)") (class "Default")
      (node (ref "X3") (pin "1") (pinfunction "1_1") (pintype "passive"))
    )
    (net (code "57") (name "unconnected-(X4-Pad1)") (class "Default")
      (node (ref "X4") (pin "1") (pinfunction "1_1") (pintype "passive"))
    )
    (net (code "58") (name "unconnected-(X5-Pad1)") (class "Default")
      (node (ref "X5") (pin "1") (pinfunction "1_1") (pintype "passive"))
    )
    (net (code "59") (name "unconnected-(X6-Pad1)") (class "Default")
      (node (ref "X6") (pin "1") (pinfunction "1_1") (pintype "passive"))
    )
    (net (code "60") (name "unconnected-(X7-Pad1)") (class "Default")
      (node (ref "X7") (pin "1") (pinfunction "1_1") (pintype "passive"))
    )
    (net (code "61") (name "unconnected-(X8-Pad1)") (class "Default")
      (node (ref "X8") (pin "1") (pinfunction "1_1") (pintype "passive"))
    )
  )
)
